# Cortex_ST-Link_Adapter.net
KiCad netlist of a schematic drawn in EAGLE
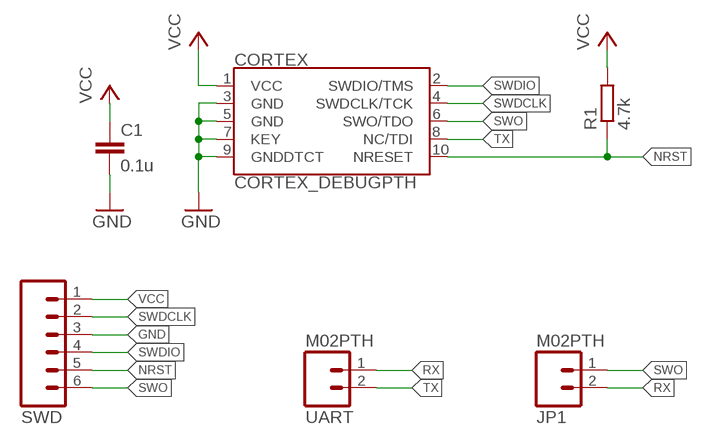
[diagram p0: schematic, sheet 1]

(export (version "E")
  (design (tool "Eeschema 10.0.6"))
  (components
    (comp (ref "C1")
      (value "0.1u")
      (footprint "eagle-import:C0805")
      (libsource (lib "eagle-import") (part "C-EUC0805"))
    )
    (comp (ref "CORTEX")
      (value "CORTEX_DEBUGPTH")
      (footprint "eagle-import:2X5-PTH-1.27MM")
      (libsource (lib "eagle-import") (part "CORTEX_DEBUGPTH"))
    )
    (comp (ref "JP1")
      (value "M02PTH")
      (footprint "eagle-import:1X02")
      (libsource (lib "eagle-import") (part "M02PTH"))
    )
    (comp (ref "R1")
      (value "4.7k")
      (footprint "eagle-import:R0805")
      (libsource (lib "eagle-import") (part "R-EU_R0805"))
    )
    (comp (ref "SWD")
      (value "M06SILK_FEMALE_PTH")
      (footprint "eagle-import:1X06")
      (libsource (lib "eagle-import") (part "M06SILK_FEMALE_PTH"))
    )
    (comp (ref "UART")
      (value "M02PTH")
      (footprint "eagle-import:1X02")
      (libsource (lib "eagle-import") (part "M02PTH"))
    )
  )
  (nets
    (net (code "1") (name "GND") (class "Default")
      (node (ref "C1") (pin "2") (pinfunction "2_2") (pintype "passive"))
      (node (ref "CORTEX") (pin "3") (pinfunction "GND_3") (pintype "bidirectional"))
      (node (ref "CORTEX") (pin "5") (pinfunction "GND_5") (pintype "bidirectional"))
      (node (ref "CORTEX") (pin "7") (pinfunction "KEY_7") (pintype "bidirectional"))
      (node (ref "CORTEX") (pin "9") (pinfunction "GNDDTCT_9") (pintype "bidirectional"))
      (node (ref "SWD") (pin "3") (pinfunction "3_3") (pintype "passive"))
    )
    (net (code "2") (name "NRST") (class "Default")
      (node (ref "CORTEX") (pin "10") (pinfunction "NRESET_10") (pintype "bidirectional"))
      (node (ref "R1") (pin "1") (pinfunction "1_1") (pintype "passive"))
      (node (ref "SWD") (pin "5") (pinfunction "5_5") (pintype "passive"))
    )
    (net (code "3") (name "RX") (class "Default")
      (node (ref "JP1") (pin "2") (pinfunction "2_2") (pintype "passive"))
      (node (ref "UART") (pin "1") (pinfunction "1_1") (pintype "passive"))
    )
    (net (code "4") (name "SWDCLK") (class "Default")
      (node (ref "CORTEX") (pin "4") (pinfunction "SWDCLK/TCK_4") (pintype "bidirectional"))
      (node (ref "SWD") (pin "2") (pinfunction "2_2") (pintype "passive"))
    )
    (net (code "5") (name "SWDIO") (class "Default")
      (node (ref "CORTEX") (pin "2") (pinfunction "SWDIO/TMS_2") (pintype "bidirectional"))
      (node (ref "SWD") (pin "4") (pinfunction "4_4") (pintype "passive"))
    )
    (net (code "6") (name "SWO") (class "Default")
      (node (ref "CORTEX") (pin "6") (pinfunction "SWO/TDO_6") (pintype "bidirectional"))
      (node (ref "JP1") (pin "1") (pinfunction "1_1") (pintype "passive"))
      (node (ref "SWD") (pin "6") (pinfunction "6_6") (pintype "passive"))
    )
    (net (code "7") (name "TX") (class "Default")
      (node (ref "CORTEX") (pin "8") (pinfunction "NC/TDI_8") (pintype "bidirectional"))
      (node (ref "UART") (pin "2") (pinfunction "2_2") (pintype "passive"))
    )
    (net (code "8") (name "VCC") (class "Default")
      (node (ref "C1") (pin "1") (pinfunction "1_1") (pintype "passive"))
      (node (ref "CORTEX") (pin "1") (pinfunction "VCC_1") (pintype "bidirectional"))
      (node (ref "R1") (pin "2") (pinfunction "2_2") (pintype "passive"))
      (node (ref "SWD") (pin "1") (pinfunction "1_1") (pintype "passive"))
    )
  )
)
